# PowerConverter.net
KiCad netlist of a schematic drawn in Altium Designer
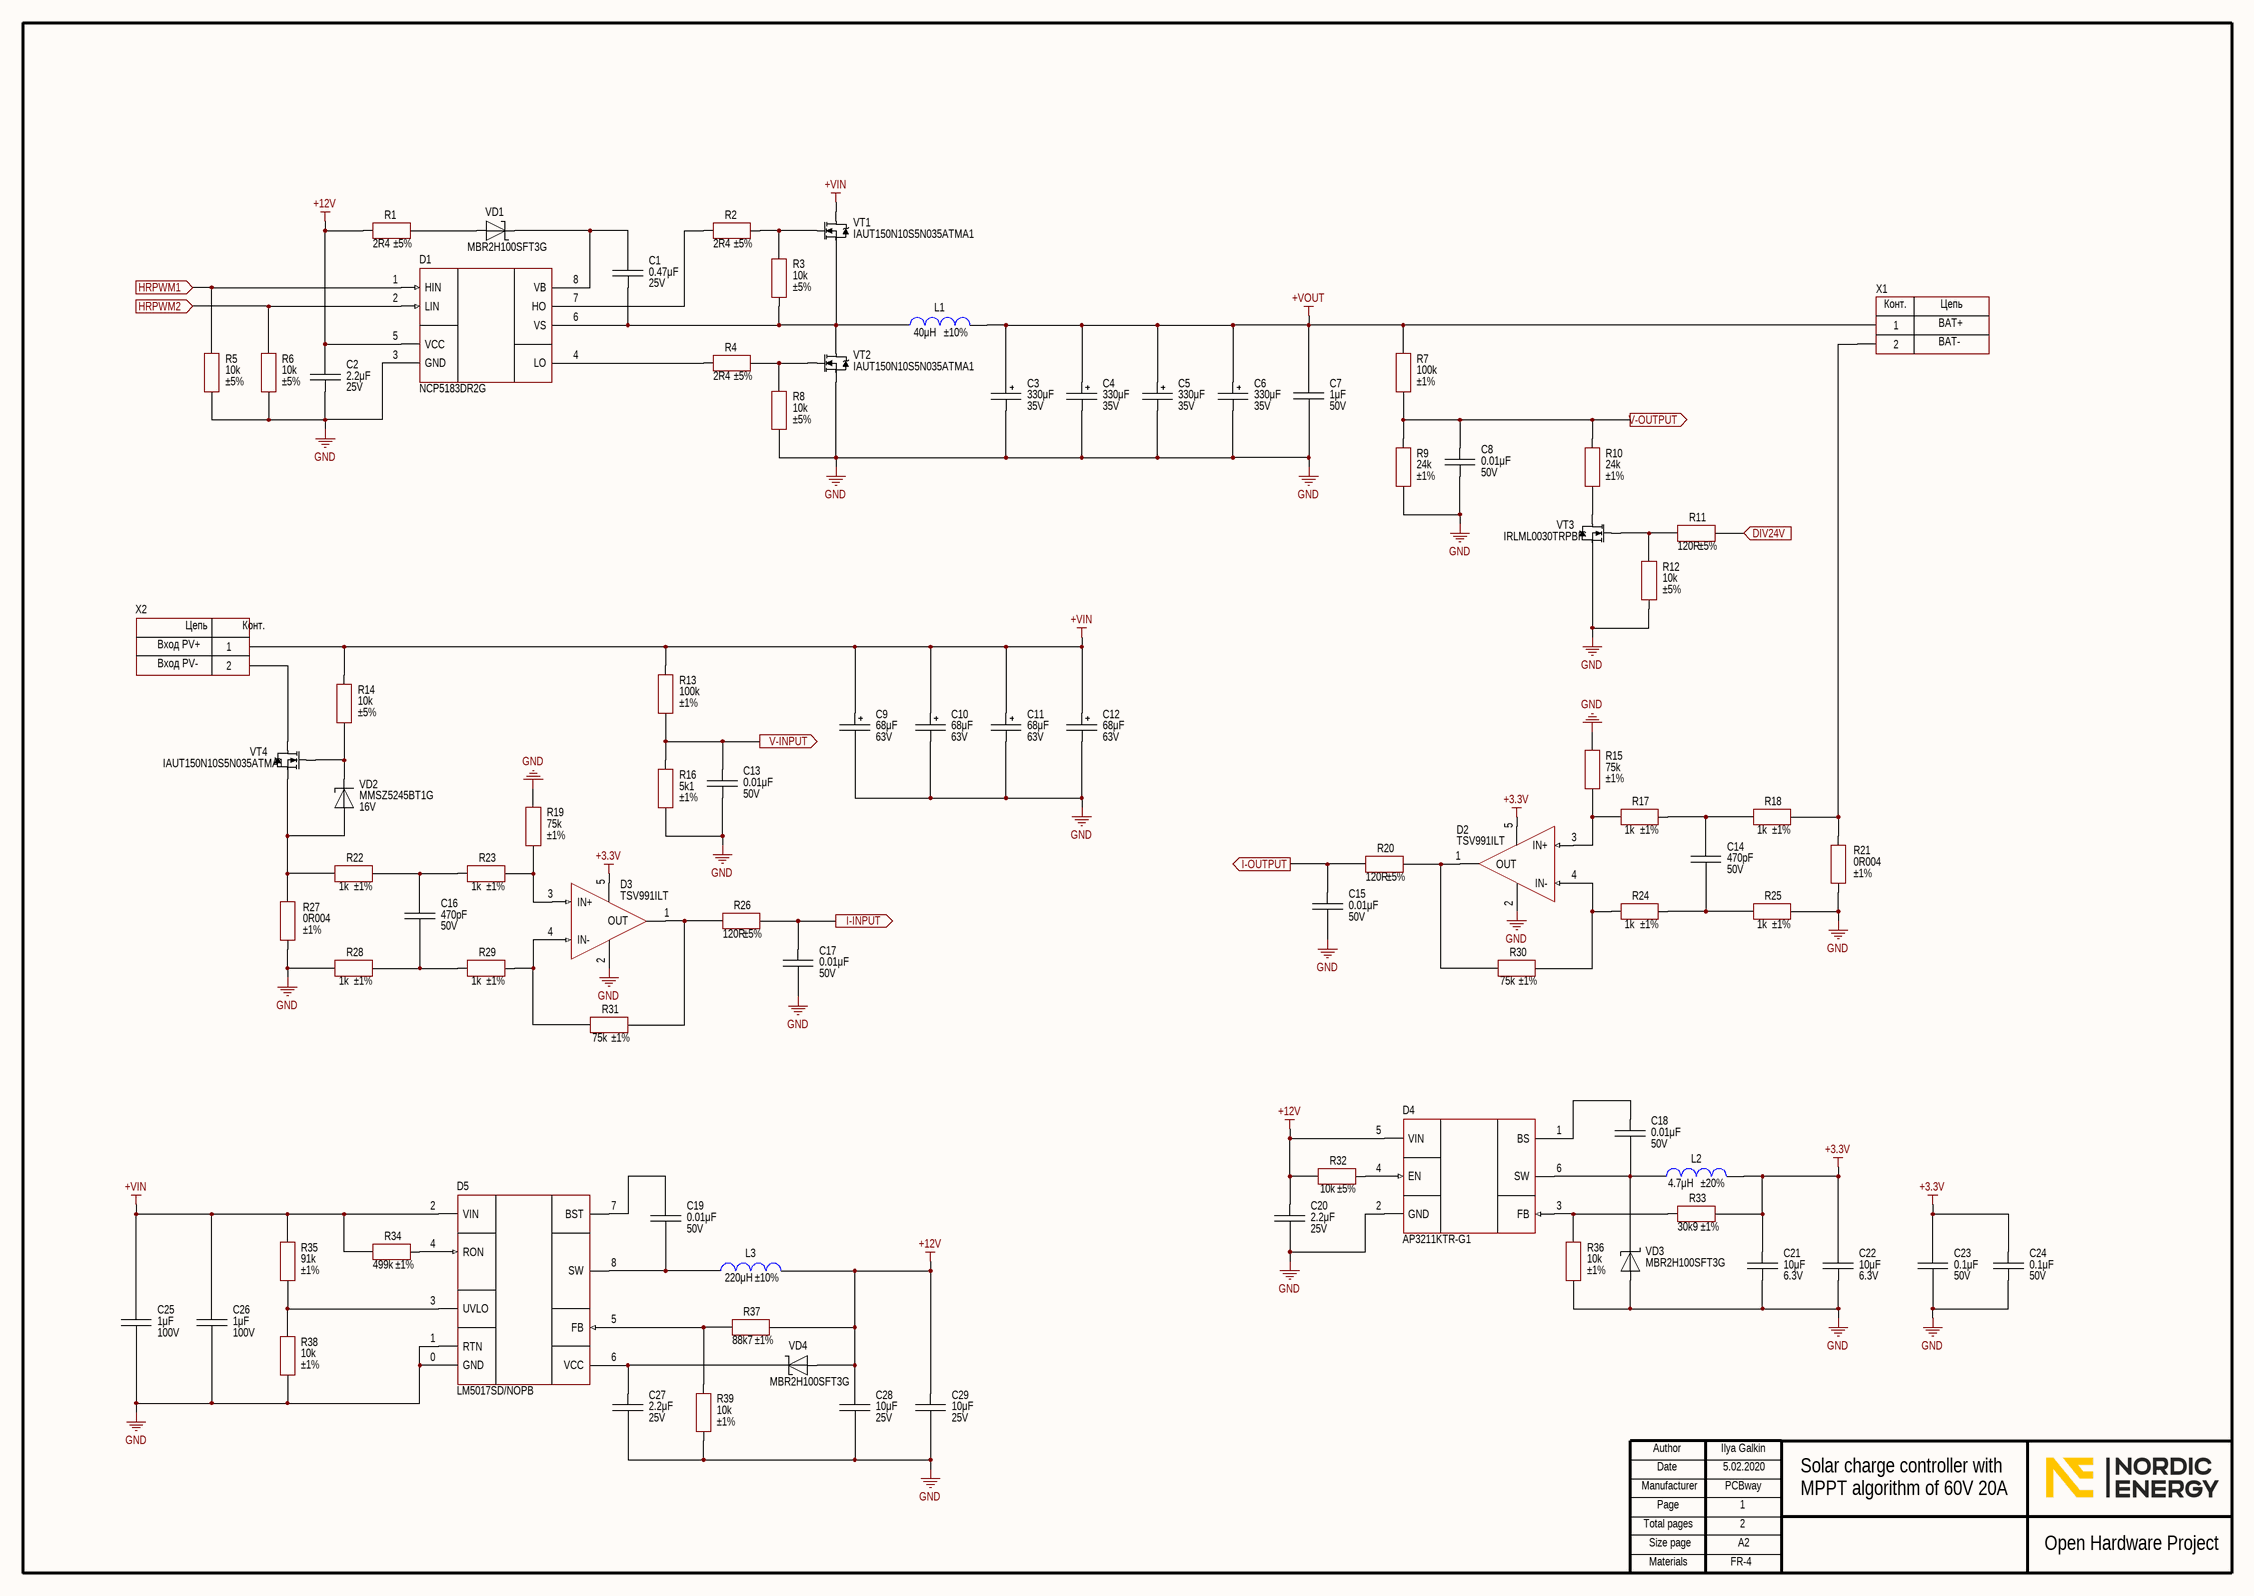
[diagram p0: PowerConverter.SchDoc]

(export (version "E")
  (design (tool "Eeschema 10.0.6"))
  (components
    (comp (ref "C1")
      (value "0.47μF")
      (footprint "CAP: 0805")
      (fields
        (field (name "MANUFACTURER") "Samsung")
        (field (name "PARTNUMBER") "CL21B474KAFNNNG")
        (field (name "VALUEMANUFACTURERPARTNUMBER") "Ceramic capacitor, 0.47μF, X7R, ±10%, 25V, 0805, -55...+125°C")
        (field (name "VOLTAGE") "25V")
      )
      (libsource (lib "Capacitor") (part "Ceramic_0805"))
    )
    (comp (ref "C2")
      (value "2.2μF")
      (footprint "CAP: 0805")
      (fields
        (field (name "MANUFACTURER") "Samsung")
        (field (name "PARTNUMBER") "CL21B225KAFNFNE")
        (field (name "VALUEMANUFACTURERPARTNUMBER") "Ceramic capacitor, 2.2μF, X7R, ±10%, 25V, 0805, -55...+125°C")
        (field (name "VOLTAGE") "25V")
      )
      (libsource (lib "Capacitor") (part "Ceramic_0805"))
    )
    (comp (ref "C3")
      (value "330μF")
      (footprint "CAP: D10C5H12.5")
      (fields
        (field (name "MANUFACTURER") "Panasonic")
        (field (name "PARTNUMBER") "35SEK330M")
        (field (name "VALUEMANUFACTURERPARTNUMBER") "Solid polymer capacitor, 330μF, 35V, ±20%, 18mOhm, 13x10x5 mm, -55...+105°C")
        (field (name "VOLTAGE") "35V")
      )
      (libsource (lib "Capacitor") (part "Aluminium"))
    )
    (comp (ref "C4")
      (value "330μF")
      (footprint "CAP: D10C5H12.5")
      (fields
        (field (name "MANUFACTURER") "Panasonic")
        (field (name "PARTNUMBER") "35SEK330M")
        (field (name "VALUEMANUFACTURERPARTNUMBER") "Solid polymer capacitor, 330μF, 35V, ±20%, 18mOhm, 13x10x5 mm, -55...+105°C")
        (field (name "VOLTAGE") "35V")
      )
      (libsource (lib "Capacitor") (part "Aluminium"))
    )
    (comp (ref "C5")
      (value "330μF")
      (footprint "CAP: D10C5H12.5")
      (fields
        (field (name "MANUFACTURER") "Panasonic")
        (field (name "PARTNUMBER") "35SEK330M")
        (field (name "VALUEMANUFACTURERPARTNUMBER") "Solid polymer capacitor, 330μF, 35V, ±20%, 18mOhm, 13x10x5 mm, -55...+105°C")
        (field (name "VOLTAGE") "35V")
      )
      (libsource (lib "Capacitor") (part "Aluminium"))
    )
    (comp (ref "C6")
      (value "330μF")
      (footprint "CAP: D10C5H12.5")
      (fields
        (field (name "MANUFACTURER") "Panasonic")
        (field (name "PARTNUMBER") "35SEK330M")
        (field (name "VALUEMANUFACTURERPARTNUMBER") "Solid polymer capacitor, 330μF, 35V, ±20%, 18mOhm, 13x10x5 mm, -55...+105°C")
        (field (name "VOLTAGE") "35V")
      )
      (libsource (lib "Capacitor") (part "Aluminium"))
    )
    (comp (ref "C7")
      (value "1μF")
      (footprint "CAP: 0805")
      (fields
        (field (name "MANUFACTURER") "Samsung")
        (field (name "PARTNUMBER") "CL21B105KBFNNNG")
        (field (name "VALUEMANUFACTURERPARTNUMBER") "Ceramic capacitor, 1μF, X7R, ±10%, 50V, 0805, -55...+125°C")
        (field (name "VOLTAGE") "50V")
      )
      (libsource (lib "Capacitor") (part "Ceramic_0805"))
    )
    (comp (ref "C8")
      (value "0.01μF")
      (footprint "CAP: 0805")
      (fields
        (field (name "MANUFACTURER") "Samsung")
        (field (name "PARTNUMBER") "CL21B103KBANNNC")
        (field (name "VALUEMANUFACTURERPARTNUMBER") "Ceramic capacitor, 0.01μF, X7R, ±10%, 50V, 0805, -55...+125°C")
        (field (name "VOLTAGE") "50V")
      )
      (libsource (lib "Capacitor") (part "Ceramic_0805"))
    )
    (comp (ref "C9")
      (value "68μF")
      (footprint "CAP: D10C5H12.5")
      (fields
        (field (name "MANUFACTURER") "Panasonic")
        (field (name "PARTNUMBER") "63SXE68M")
        (field (name "VALUEMANUFACTURERPARTNUMBER") "Solid polymer capacitor, 68μF, 63V, ±20%, 25mOhm, 13x10x5 mm, -55...+105°C")
        (field (name "VOLTAGE") "63V")
      )
      (libsource (lib "Capacitor") (part "Aluminium"))
    )
    (comp (ref "C10")
      (value "68μF")
      (footprint "CAP: D10C5H12.5")
      (fields
        (field (name "MANUFACTURER") "Panasonic")
        (field (name "PARTNUMBER") "63SXE68M")
        (field (name "VALUEMANUFACTURERPARTNUMBER") "Solid polymer capacitor, 68μF, 63V, ±20%, 25mOhm, 13x10x5 mm, -55...+105°C")
        (field (name "VOLTAGE") "63V")
      )
      (libsource (lib "Capacitor") (part "Aluminium"))
    )
    (comp (ref "C11")
      (value "68μF")
      (footprint "CAP: D10C5H12.5")
      (fields
        (field (name "MANUFACTURER") "Panasonic")
        (field (name "PARTNUMBER") "63SXE68M")
        (field (name "VALUEMANUFACTURERPARTNUMBER") "Solid polymer capacitor, 68μF, 63V, ±20%, 25mOhm, 13x10x5 mm, -55...+105°C")
        (field (name "VOLTAGE") "63V")
      )
      (libsource (lib "Capacitor") (part "Aluminium"))
    )
    (comp (ref "C12")
      (value "68μF")
      (footprint "CAP: D10C5H12.5")
      (fields
        (field (name "MANUFACTURER") "Panasonic")
        (field (name "PARTNUMBER") "63SXE68M")
        (field (name "VALUEMANUFACTURERPARTNUMBER") "Solid polymer capacitor, 68μF, 63V, ±20%, 25mOhm, 13x10x5 mm, -55...+105°C")
        (field (name "VOLTAGE") "63V")
      )
      (libsource (lib "Capacitor") (part "Aluminium"))
    )
    (comp (ref "C13")
      (value "0.01μF")
      (footprint "CAP: 0805")
      (fields
        (field (name "MANUFACTURER") "Samsung")
        (field (name "PARTNUMBER") "CL21B103KBANNNC")
        (field (name "VALUEMANUFACTURERPARTNUMBER") "Ceramic capacitor, 0.01μF, X7R, ±10%, 50V, 0805, -55...+125°C")
        (field (name "VOLTAGE") "50V")
      )
      (libsource (lib "Capacitor") (part "Ceramic_0805"))
    )
    (comp (ref "C14")
      (value "470pF")
      (footprint "CAP: 0805")
      (fields
        (field (name "MANUFACTURER") "Samsung")
        (field (name "PARTNUMBER") "CL21B471KBANNNC")
        (field (name "VALUEMANUFACTURERPARTNUMBER") "Ceramic capacitor, 470pF, X7R, ±10%, 50V, 0805, -55...+125°C")
        (field (name "VOLTAGE") "50V")
      )
      (libsource (lib "Capacitor") (part "Ceramic_0805"))
    )
    (comp (ref "C15")
      (value "0.01μF")
      (footprint "CAP: 0805")
      (fields
        (field (name "MANUFACTURER") "Samsung")
        (field (name "PARTNUMBER") "CL21B103KBANNNC")
        (field (name "VALUEMANUFACTURERPARTNUMBER") "Ceramic capacitor, 0.01μF, X7R, ±10%, 50V, 0805, -55...+125°C")
        (field (name "VOLTAGE") "50V")
      )
      (libsource (lib "Capacitor") (part "Ceramic_0805"))
    )
    (comp (ref "C16")
      (value "470pF")
      (footprint "CAP: 0805")
      (fields
        (field (name "MANUFACTURER") "Samsung")
        (field (name "PARTNUMBER") "CL21B471KBANNNC")
        (field (name "VALUEMANUFACTURERPARTNUMBER") "Ceramic capacitor, 470pF, X7R, ±10%, 50V, 0805, -55...+125°C")
        (field (name "VOLTAGE") "50V")
      )
      (libsource (lib "Capacitor") (part "Ceramic_0805"))
    )
    (comp (ref "C17")
      (value "0.01μF")
      (footprint "CAP: 0805")
      (fields
        (field (name "MANUFACTURER") "Samsung")
        (field (name "PARTNUMBER") "CL21B103KBANNNC")
        (field (name "VALUEMANUFACTURERPARTNUMBER") "Ceramic capacitor, 0.01μF, X7R, ±10%, 50V, 0805, -55...+125°C")
        (field (name "VOLTAGE") "50V")
      )
      (libsource (lib "Capacitor") (part "Ceramic_0805"))
    )
    (comp (ref "C18")
      (value "0.01μF")
      (footprint "CAP: 0805")
      (fields
        (field (name "MANUFACTURER") "Samsung")
        (field (name "PARTNUMBER") "CL21B103KBANNNC")
        (field (name "VALUEMANUFACTURERPARTNUMBER") "Ceramic capacitor, 0.01μF, X7R, ±10%, 50V, 0805, -55...+125°C")
        (field (name "VOLTAGE") "50V")
      )
      (libsource (lib "Capacitor") (part "Ceramic_0805"))
    )
    (comp (ref "C19")
      (value "0.01μF")
      (footprint "CAP: 0805")
      (fields
        (field (name "MANUFACTURER") "Samsung")
        (field (name "PARTNUMBER") "CL21B103KBANNNC")
        (field (name "VALUEMANUFACTURERPARTNUMBER") "Ceramic capacitor, 0.01μF, X7R, ±10%, 50V, 0805, -55...+125°C")
        (field (name "VOLTAGE") "50V")
      )
      (libsource (lib "Capacitor") (part "Ceramic_0805"))
    )
    (comp (ref "C20")
      (value "2.2μF")
      (footprint "CAP: 0805")
      (fields
        (field (name "MANUFACTURER") "Samsung")
        (field (name "PARTNUMBER") "CL21B225KAFNFNE")
        (field (name "VALUEMANUFACTURERPARTNUMBER") "Ceramic capacitor, 2.2μF, X7R, ±10%, 25V, 0805, -55...+125°C")
        (field (name "VOLTAGE") "25V")
      )
      (libsource (lib "Capacitor") (part "Ceramic_0805"))
    )
    (comp (ref "C21")
      (value "10μF")
      (footprint "CAP: 0805")
      (fields
        (field (name "MANUFACTURER") "Samsung")
        (field (name "PARTNUMBER") "CL21B106KQQNNNG")
        (field (name "VALUEMANUFACTURERPARTNUMBER") "Ceramic capacitor, 10μF, X7R, ±10%, 6.3V, 0805, -55...+125°C")
        (field (name "VOLTAGE") "6.3V")
      )
      (libsource (lib "Capacitor") (part "Ceramic_0805"))
    )
    (comp (ref "C22")
      (value "10μF")
      (footprint "CAP: 0805")
      (fields
        (field (name "MANUFACTURER") "Samsung")
        (field (name "PARTNUMBER") "CL21B106KQQNNNG")
        (field (name "VALUEMANUFACTURERPARTNUMBER") "Ceramic capacitor, 10μF, X7R, ±10%, 6.3V, 0805, -55...+125°C")
        (field (name "VOLTAGE") "6.3V")
      )
      (libsource (lib "Capacitor") (part "Ceramic_0805"))
    )
    (comp (ref "C23")
      (value "0.1μF")
      (footprint "CAP: 0805")
      (fields
        (field (name "MANUFACTURER") "Samsung")
        (field (name "PARTNUMBER") "CL21B104KBCNFNC")
        (field (name "VALUEMANUFACTURERPARTNUMBER") "Ceramic capacitor, 0.1μF, X7R, ±10%, 50V, 0805, -55...+125°C")
        (field (name "VOLTAGE") "50V")
      )
      (libsource (lib "Capacitor") (part "Ceramic_0805"))
    )
    (comp (ref "C24")
      (value "0.1μF")
      (footprint "CAP: 0805")
      (fields
        (field (name "MANUFACTURER") "Samsung")
        (field (name "PARTNUMBER") "CL21B104KBCNFNC")
        (field (name "VALUEMANUFACTURERPARTNUMBER") "Ceramic capacitor, 0.1μF, X7R, ±10%, 50V, 0805, -55...+125°C")
        (field (name "VOLTAGE") "50V")
      )
      (libsource (lib "Capacitor") (part "Ceramic_0805"))
    )
    (comp (ref "C25")
      (value "1μF")
      (footprint "CAP: 1206")
      (fields
        (field (name "MANUFACTURER") "Samsung")
        (field (name "PARTNUMBER") "CL31B105KCHSNNE")
        (field (name "VALUEMANUFACTURERPARTNUMBER") "Ceramic capacitor, 1μF, X7R, ±10%, 100V, 1206, -55...+125°C")
        (field (name "VOLTAGE") "100V")
      )
      (libsource (lib "Capacitor") (part "Ceramic_1206"))
    )
    (comp (ref "C26")
      (value "1μF")
      (footprint "CAP: 1206")
      (fields
        (field (name "MANUFACTURER") "Samsung")
        (field (name "PARTNUMBER") "CL31B105KCHSNNE")
        (field (name "VALUEMANUFACTURERPARTNUMBER") "Ceramic capacitor, 1μF, X7R, ±10%, 100V, 1206, -55...+125°C")
        (field (name "VOLTAGE") "100V")
      )
      (libsource (lib "Capacitor") (part "Ceramic_1206"))
    )
    (comp (ref "C27")
      (value "2.2μF")
      (footprint "CAP: 0805")
      (fields
        (field (name "MANUFACTURER") "Samsung")
        (field (name "PARTNUMBER") "CL21B225KAFNFNE")
        (field (name "VALUEMANUFACTURERPARTNUMBER") "Ceramic capacitor, 2.2μF, X7R, ±10%, 25V, 0805, -55...+125°C")
        (field (name "VOLTAGE") "25V")
      )
      (libsource (lib "Capacitor") (part "Ceramic_0805"))
    )
    (comp (ref "C28")
      (value "10μF")
      (footprint "CAP: 1206")
      (fields
        (field (name "MANUFACTURER") "Samsung")
        (field (name "PARTNUMBER") "CL31B106KAHNNNE")
        (field (name "VALUEMANUFACTURERPARTNUMBER") "Ceramic capacitor, 10μF, X7R, ±10%, 25V, 1206, -55...+125°C")
        (field (name "VOLTAGE") "25V")
      )
      (libsource (lib "Capacitor") (part "Ceramic_1206"))
    )
    (comp (ref "C29")
      (value "10μF")
      (footprint "CAP: 1206")
      (fields
        (field (name "MANUFACTURER") "Samsung")
        (field (name "PARTNUMBER") "CL31B106KAHNNNE")
        (field (name "VALUEMANUFACTURERPARTNUMBER") "Ceramic capacitor, 10μF, X7R, ±10%, 25V, 1206, -55...+125°C")
        (field (name "VOLTAGE") "25V")
      )
      (libsource (lib "Capacitor") (part "Ceramic_1206"))
    )
    (comp (ref "D1")
      (value "~")
      (footprint "8-SOIC")
      (description "Gate driver")
      (fields
        (field (name "MANUFACTURER") "ON Semiconductor")
        (field (name "VALUEMANUFACTURERPARTNUMBER") "Half-bridge gate driver, 600V, 500kHz, ±4.3A, supply 9...18V, -40...+125°C, 8-SOIC")
        (field (name "PARTNUMBER") "NCP5183DR2G")
      )
      (libsource (lib "IC. Gate driver") (part "NCP5183DR2G"))
    )
    (comp (ref "D2")
      (value "~")
      (footprint "SOT23-5")
      (description "OP amplifier")
      (fields
        (field (name "MANUFACTURER") "STMicroelectronics")
        (field (name "VALUEMANUFACTURERPARTNUMBER") "IC op amplifier, Rail-to-Rail, 20 MHz, 2.7...5.5V, -40...+125°C, SOT23-5")
        (field (name "PARTNUMBER") "TSV991ILT")
      )
      (libsource (lib "IC. Amplifier") (part "TSV991ILT"))
    )
    (comp (ref "D3")
      (value "~")
      (footprint "SOT23-5")
      (description "OP amplifier")
      (fields
        (field (name "MANUFACTURER") "STMicroelectronics")
        (field (name "VALUEMANUFACTURERPARTNUMBER") "IC op amplifier, Rail-to-Rail, 20 MHz, 2.7...5.5V, -40...+125°C, SOT23-5")
        (field (name "PARTNUMBER") "TSV991ILT")
      )
      (libsource (lib "IC. Amplifier") (part "TSV991ILT"))
    )
    (comp (ref "D4")
      (value "~")
      (footprint "SOT23-6")
      (description "Buck converter")
      (fields
        (field (name "MANUFACTURER") "Diodes Incorporated")
        (field (name "VALUEMANUFACTURERPARTNUMBER") "DC/DC buck converter, input 4.5...18V, 1.4MHz, output 0.81...15V, 1.5A, -40...+85°C, SOT23-6")
        (field (name "PARTNUMBER") "AP3211KTR-G1")
      )
      (libsource (lib "IC. Power supply") (part "AP3211KTR-G1"))
    )
    (comp (ref "D5")
      (value "~")
      (footprint "8-WSON (4x4)")
      (description "Buck converter")
      (fields
        (field (name "MANUFACTURER") "Texas Instruments")
        (field (name "VALUEMANUFACTURERPARTNUMBER") "DC/DC buck converter, input 7.5...100V, 1MHz, output 1.225...90V, 0.6A, -40...+125°C, 8-WSON")
        (field (name "PARTNUMBER") "LM5017SD/NOPB")
      )
      (libsource (lib "IC. Power supply") (part "LM5017SD"))
    )
    (comp (ref "L1")
      (value "40μH")
      (footprint "IND: R32.8/20.1/10.7 (L)")
      (fields
        (field (name "MANUFACTURER") "Magnetics")
        (field (name "PARTNUMBER") "0077548A7")
        (field (name "VALUEMANUFACTURERPARTNUMBER") "Fixed inductor, 40μH, ±10%, R32.8/20.1/10.7, Kool Mu, µ=125, 127 нГн/витков2")
        (field (name "TOLERANCE") "±10%")
      )
      (libsource (lib "Inductor") (part "Inductor_R32.8/20.1/10.7"))
    )
    (comp (ref "L2")
      (value "4.7μH")
      (footprint "IND: SDR0403")
      (fields
        (field (name "MANUFACTURER") "Bourns")
        (field (name "PARTNUMBER") "SDR0403-4R7ML")
        (field (name "VALUEMANUFACTURERPARTNUMBER") "Fixed inductor, 4.7μH, ±20%, SDR0403, 1.7A, -40...+125°C")
        (field (name "TOLERANCE") "±20%")
      )
      (libsource (lib "Inductor") (part "Inductor_SDR0403"))
    )
    (comp (ref "L3")
      (value "220μH")
      (footprint "IND: SDR0805")
      (fields
        (field (name "MANUFACTURER") "Bourns")
        (field (name "PARTNUMBER") "SDR0805-221KL")
        (field (name "VALUEMANUFACTURERPARTNUMBER") "Fixed inductor, 220μH, ±10%, SDR0805, 490mA, -40...+125°C")
        (field (name "TOLERANCE") "±10%")
      )
      (libsource (lib "Inductor") (part "Inductor_SDR0805"))
    )
    (comp (ref "R1")
      (value "2R4")
      (footprint "RES: 0805")
      (fields
        (field (name "MANUFACTURER") "Yageo")
        (field (name "PARTNUMBER") "RC0805JR-072R4L")
        (field (name "VALUEMANUFACTURERPARTNUMBER") "Resistor film, 2R4, ±5%, 0805, 0.125W, -55...+125°C")
        (field (name "TOLERANCE") "±5%")
      )
      (libsource (lib "Resistor") (part "Resistor_0805"))
    )
    (comp (ref "R2")
      (value "2R4")
      (footprint "RES: 0805")
      (fields
        (field (name "MANUFACTURER") "Yageo")
        (field (name "PARTNUMBER") "RC0805JR-072R4L")
        (field (name "VALUEMANUFACTURERPARTNUMBER") "Resistor film, 2R4, ±5%, 0805, 0.125W, -55...+125°C")
        (field (name "TOLERANCE") "±5%")
      )
      (libsource (lib "Resistor") (part "Resistor_0805"))
    )
    (comp (ref "R3")
      (value "10k")
      (footprint "RES: 0805")
      (fields
        (field (name "MANUFACTURER") "Yageo")
        (field (name "PARTNUMBER") "RC0805JR-0710KL")
        (field (name "VALUEMANUFACTURERPARTNUMBER") "Resistor film, 10k, ±5%, 0805, 0.125W, -55...+125°C")
        (field (name "TOLERANCE") "±5%")
      )
      (libsource (lib "") (part "Resistor_0805_1"))
    )
    (comp (ref "R4")
      (value "2R4")
      (footprint "RES: 0805")
      (fields
        (field (name "MANUFACTURER") "Yageo")
        (field (name "PARTNUMBER") "RC0805JR-072R4L")
        (field (name "VALUEMANUFACTURERPARTNUMBER") "Resistor film, 2R4, ±5%, 0805, 0.125W, -55...+125°C")
        (field (name "TOLERANCE") "±5%")
      )
      (libsource (lib "Resistor") (part "Resistor_0805"))
    )
    (comp (ref "R5")
      (value "10k")
      (footprint "RES: 0805")
      (fields
        (field (name "MANUFACTURER") "Yageo")
        (field (name "PARTNUMBER") "RC0805JR-0710KL")
        (field (name "VALUEMANUFACTURERPARTNUMBER") "Resistor film, 10k, ±5%, 0805, 0.125W, -55...+125°C")
        (field (name "TOLERANCE") "±5%")
      )
      (libsource (lib "") (part "Resistor_0805_1"))
    )
    (comp (ref "R6")
      (value "10k")
      (footprint "RES: 0805")
      (fields
        (field (name "MANUFACTURER") "Yageo")
        (field (name "PARTNUMBER") "RC0805JR-0710KL")
        (field (name "VALUEMANUFACTURERPARTNUMBER") "Resistor film, 10k, ±5%, 0805, 0.125W, -55...+125°C")
        (field (name "TOLERANCE") "±5%")
      )
      (libsource (lib "") (part "Resistor_0805_1"))
    )
    (comp (ref "R7")
      (value "100k")
      (footprint "RES: 0805")
      (fields
        (field (name "MANUFACTURER") "Yageo")
        (field (name "PARTNUMBER") "RC0805FR-07100KL")
        (field (name "VALUEMANUFACTURERPARTNUMBER") "Resistor film, 100k, ±1%, 0805, 0.125W, -55...+125°C")
        (field (name "TOLERANCE") "±1%")
      )
      (libsource (lib "") (part "Resistor_0805_1"))
    )
    (comp (ref "R8")
      (value "10k")
      (footprint "RES: 0805")
      (fields
        (field (name "MANUFACTURER") "Yageo")
        (field (name "PARTNUMBER") "RC0805JR-0710KL")
        (field (name "VALUEMANUFACTURERPARTNUMBER") "Resistor film, 10k, ±5%, 0805, 0.125W, -55...+125°C")
        (field (name "TOLERANCE") "±5%")
      )
      (libsource (lib "") (part "Resistor_0805_1"))
    )
    (comp (ref "R9")
      (value "24k")
      (footprint "RES: 0805")
      (fields
        (field (name "MANUFACTURER") "Yageo")
        (field (name "PARTNUMBER") "RC0805FR-0724KL")
        (field (name "VALUEMANUFACTURERPARTNUMBER") "Resistor film, 24k, ±1%, 0805, 0.125W, -55...+125°C")
        (field (name "TOLERANCE") "±1%")
      )
      (libsource (lib "") (part "Resistor_0805_1"))
    )
    (comp (ref "R10")
      (value "24k")
      (footprint "RES: 0805")
      (fields
        (field (name "MANUFACTURER") "Yageo")
        (field (name "PARTNUMBER") "RC0805FR-0724KL")
        (field (name "VALUEMANUFACTURERPARTNUMBER") "Resistor film, 24k, ±1%, 0805, 0.125W, -55...+125°C")
        (field (name "TOLERANCE") "±1%")
      )
      (libsource (lib "") (part "Resistor_0805_1"))
    )
    (comp (ref "R11")
      (value "120R")
      (footprint "RES: 0805")
      (fields
        (field (name "MANUFACTURER") "Yageo")
        (field (name "PARTNUMBER") "RC0805JR-07120RL")
        (field (name "VALUEMANUFACTURERPARTNUMBER") "Resistor film, 120R, ±5%, 0805, 0.125W, -55...+125°C")
        (field (name "TOLERANCE") "±5%")
      )
      (libsource (lib "Resistor") (part "Resistor_0805"))
    )
    (comp (ref "R12")
      (value "10k")
      (footprint "RES: 0805")
      (fields
        (field (name "MANUFACTURER") "Yageo")
        (field (name "PARTNUMBER") "RC0805JR-0710KL")
        (field (name "VALUEMANUFACTURERPARTNUMBER") "Resistor film, 10k, ±5%, 0805, 0.125W, -55...+125°C")
        (field (name "TOLERANCE") "±5%")
      )
      (libsource (lib "") (part "Resistor_0805_1"))
    )
    (comp (ref "R13")
      (value "100k")
      (footprint "RES: 0805")
      (fields
        (field (name "MANUFACTURER") "Yageo")
        (field (name "PARTNUMBER") "RC0805FR-07100KL")
        (field (name "VALUEMANUFACTURERPARTNUMBER") "Resistor film, 100k, ±1%, 0805, 0.125W, -55...+125°C")
        (field (name "TOLERANCE") "±1%")
      )
      (libsource (lib "") (part "Resistor_0805_1"))
    )
    (comp (ref "R14")
      (value "10k")
      (footprint "RES: 0805")
      (fields
        (field (name "MANUFACTURER") "Yageo")
        (field (name "PARTNUMBER") "RC0805JR-0710KL")
        (field (name "VALUEMANUFACTURERPARTNUMBER") "Resistor film, 10k, ±5%, 0805, 0.125W, -55...+125°C")
        (field (name "TOLERANCE") "±5%")
      )
      (libsource (lib "") (part "Resistor_0805_1"))
    )
    (comp (ref "R15")
      (value "75k")
      (footprint "RES: 0805")
      (fields
        (field (name "MANUFACTURER") "Yageo")
        (field (name "PARTNUMBER") "RC0805FR-0775KL")
        (field (name "VALUEMANUFACTURERPARTNUMBER") "Resistor film, 75k, ±1%, 0805, 0.125W, -55...+125°C")
        (field (name "TOLERANCE") "±1%")
      )
      (libsource (lib "") (part "Resistor_0805_1"))
    )
    (comp (ref "R16")
      (value "5k1")
      (footprint "RES: 0805")
      (fields
        (field (name "MANUFACTURER") "Yageo")
        (field (name "PARTNUMBER") "RC0805FR-075K1L")
        (field (name "VALUEMANUFACTURERPARTNUMBER") "Resistor film, 5k1, ±1%, 0805, 0.125W, -55...+125°C")
        (field (name "TOLERANCE") "±1%")
      )
      (libsource (lib "") (part "Resistor_0805_1"))
    )
    (comp (ref "R17")
      (value "1k")
      (footprint "RES: 0805")
      (fields
        (field (name "MANUFACTURER") "Yageo")
        (field (name "PARTNUMBER") "RC0805FR-071KL")
        (field (name "VALUEMANUFACTURERPARTNUMBER") "Resistor film, 1k, ±1%, 0805, 0.125W, -55...+125°C")
        (field (name "TOLERANCE") "±1%")
      )
      (libsource (lib "Resistor") (part "Resistor_0805"))
    )
    (comp (ref "R18")
      (value "1k")
      (footprint "RES: 0805")
      (fields
        (field (name "MANUFACTURER") "Yageo")
        (field (name "PARTNUMBER") "RC0805FR-071KL")
        (field (name "VALUEMANUFACTURERPARTNUMBER") "Resistor film, 1k, ±1%, 0805, 0.125W, -55...+125°C")
        (field (name "TOLERANCE") "±1%")
      )
      (libsource (lib "Resistor") (part "Resistor_0805"))
    )
    (comp (ref "R19")
      (value "75k")
      (footprint "RES: 0805")
      (fields
        (field (name "MANUFACTURER") "Yageo")
        (field (name "PARTNUMBER") "RC0805FR-0775KL")
        (field (name "VALUEMANUFACTURERPARTNUMBER") "Resistor film, 75k, ±1%, 0805, 0.125W, -55...+125°C")
        (field (name "TOLERANCE") "±1%")
      )
      (libsource (lib "") (part "Resistor_0805_1"))
    )
    (comp (ref "R20")
      (value "120R")
      (footprint "RES: 0805")
      (fields
        (field (name "MANUFACTURER") "Yageo")
        (field (name "PARTNUMBER") "RC0805JR-07120RL")
        (field (name "VALUEMANUFACTURERPARTNUMBER") "Resistor film, 120R, ±5%, 0805, 0.125W, -55...+125°C")
        (field (name "TOLERANCE") "±5%")
      )
      (libsource (lib "Resistor") (part "Resistor_0805"))
    )
    (comp (ref "R21")
      (value "0R004")
      (footprint "RES: CSS2H (2512)")
      (fields
        (field (name "MANUFACTURER") "Bourns")
        (field (name "PARTNUMBER") "CRE2512-FZ-R004E-3")
        (field (name "VALUEMANUFACTURERPARTNUMBER") "Resistor film, 0R004, ±1%, 2512, 5W, -55...+170°C")
        (field (name "TOLERANCE") "±1%")
      )
      (libsource (lib "Resistor") (part "Shunt"))
    )
    (comp (ref "R22")
      (value "1k")
      (footprint "RES: 0805")
      (fields
        (field (name "MANUFACTURER") "Yageo")
        (field (name "PARTNUMBER") "RC0805FR-071KL")
        (field (name "VALUEMANUFACTURERPARTNUMBER") "Resistor film, 1k, ±1%, 0805, 0.125W, -55...+125°C")
        (field (name "TOLERANCE") "±1%")
      )
      (libsource (lib "Resistor") (part "Resistor_0805"))
    )
    (comp (ref "R23")
      (value "1k")
      (footprint "RES: 0805")
      (fields
        (field (name "MANUFACTURER") "Yageo")
        (field (name "PARTNUMBER") "RC0805FR-071KL")
        (field (name "VALUEMANUFACTURERPARTNUMBER") "Resistor film, 1k, ±1%, 0805, 0.125W, -55...+125°C")
        (field (name "TOLERANCE") "±1%")
      )
      (libsource (lib "Resistor") (part "Resistor_0805"))
    )
    (comp (ref "R24")
      (value "1k")
      (footprint "RES: 0805")
      (fields
        (field (name "MANUFACTURER") "Yageo")
        (field (name "PARTNUMBER") "RC0805FR-071KL")
        (field (name "VALUEMANUFACTURERPARTNUMBER") "Resistor film, 1k, ±1%, 0805, 0.125W, -55...+125°C")
        (field (name "TOLERANCE") "±1%")
      )
      (libsource (lib "Resistor") (part "Resistor_0805"))
    )
    (comp (ref "R25")
      (value "1k")
      (footprint "RES: 0805")
      (fields
        (field (name "MANUFACTURER") "Yageo")
        (field (name "PARTNUMBER") "RC0805FR-071KL")
        (field (name "VALUEMANUFACTURERPARTNUMBER") "Resistor film, 1k, ±1%, 0805, 0.125W, -55...+125°C")
        (field (name "TOLERANCE") "±1%")
      )
      (libsource (lib "Resistor") (part "Resistor_0805"))
    )
    (comp (ref "R26")
      (value "120R")
      (footprint "RES: 0805")
      (fields
        (field (name "MANUFACTURER") "Yageo")
        (field (name "PARTNUMBER") "RC0805JR-07120RL")
        (field (name "VALUEMANUFACTURERPARTNUMBER") "Resistor film, 120R, ±5%, 0805, 0.125W, -55...+125°C")
        (field (name "TOLERANCE") "±5%")
      )
      (libsource (lib "Resistor") (part "Resistor_0805"))
    )
    (comp (ref "R27")
      (value "0R004")
      (footprint "RES: CSS2H (2512)")
      (fields
        (field (name "MANUFACTURER") "Bourns")
        (field (name "PARTNUMBER") "CRE2512-FZ-R004E-3")
        (field (name "VALUEMANUFACTURERPARTNUMBER") "Resistor film, 0R004, ±1%, 2512, 5W, -55...+170°C")
        (field (name "TOLERANCE") "±1%")
      )
      (libsource (lib "Resistor") (part "Shunt"))
    )
    (comp (ref "R28")
      (value "1k")
      (footprint "RES: 0805")
      (fields
        (field (name "MANUFACTURER") "Yageo")
        (field (name "PARTNUMBER") "RC0805FR-071KL")
        (field (name "VALUEMANUFACTURERPARTNUMBER") "Resistor film, 1k, ±1%, 0805, 0.125W, -55...+125°C")
        (field (name "TOLERANCE") "±1%")
      )
      (libsource (lib "Resistor") (part "Resistor_0805"))
    )
    (comp (ref "R29")
      (value "1k")
      (footprint "RES: 0805")
      (fields
        (field (name "MANUFACTURER") "Yageo")
        (field (name "PARTNUMBER") "RC0805FR-071KL")
        (field (name "VALUEMANUFACTURERPARTNUMBER") "Resistor film, 1k, ±1%, 0805, 0.125W, -55...+125°C")
        (field (name "TOLERANCE") "±1%")
      )
      (libsource (lib "Resistor") (part "Resistor_0805"))
    )
    (comp (ref "R30")
      (value "75k")
      (footprint "RES: 0805")
      (fields
        (field (name "MANUFACTURER") "Yageo")
        (field (name "PARTNUMBER") "RC0805FR-0775KL")
        (field (name "VALUEMANUFACTURERPARTNUMBER") "Resistor film, 75k, ±1%, 0805, 0.125W, -55...+125°C")
        (field (name "TOLERANCE") "±1%")
      )
      (libsource (lib "Resistor") (part "Resistor_0805"))
    )
    (comp (ref "R31")
      (value "75k")
      (footprint "RES: 0805")
      (fields
        (field (name "MANUFACTURER") "Yageo")
        (field (name "PARTNUMBER") "RC0805FR-0775KL")
        (field (name "VALUEMANUFACTURERPARTNUMBER") "Resistor film, 75k, ±1%, 0805, 0.125W, -55...+125°C")
        (field (name "TOLERANCE") "±1%")
      )
      (libsource (lib "Resistor") (part "Resistor_0805"))
    )
    (comp (ref "R32")
      (value "10k")
      (footprint "RES: 0805")
      (fields
        (field (name "MANUFACTURER") "Yageo")
        (field (name "PARTNUMBER") "RC0805JR-0710KL")
        (field (name "VALUEMANUFACTURERPARTNUMBER") "Resistor film, 10k, ±5%, 0805, 0.125W, -55...+125°C")
        (field (name "TOLERANCE") "±5%")
      )
      (libsource (lib "Resistor") (part "Resistor_0805"))
    )
    (comp (ref "R33")
      (value "30k9")
      (footprint "RES: 0805")
      (fields
        (field (name "MANUFACTURER") "Yageo")
        (field (name "PARTNUMBER") "RC0805FR-0730K9L")
        (field (name "VALUEMANUFACTURERPARTNUMBER") "Resistor film, 30k9, ±1%, 0805, 0.125W, -55...+125°C")
        (field (name "TOLERANCE") "±1%")
      )
      (libsource (lib "Resistor") (part "Resistor_0805"))
    )
    (comp (ref "R34")
      (value "499k")
      (footprint "RES: 0805")
      (fields
        (field (name "MANUFACTURER") "Yageo")
        (field (name "PARTNUMBER") "RC0805FR-07499KL")
        (field (name "VALUEMANUFACTURERPARTNUMBER") "Resistor film, 499k, ±1%, 0805, 0.125W, -55...+125°C")
        (field (name "TOLERANCE") "±1%")
      )
      (libsource (lib "Resistor") (part "Resistor_0805"))
    )
    (comp (ref "R35")
      (value "91k")
      (footprint "RES: 0805")
      (fields
        (field (name "MANUFACTURER") "Yageo")
        (field (name "PARTNUMBER") "RC0805FR-0791KL")
        (field (name "VALUEMANUFACTURERPARTNUMBER") "Resistor film, 91k, ±1%, 0805, 0.125W, -55...+125°C")
        (field (name "TOLERANCE") "±1%")
      )
      (libsource (lib "") (part "Resistor_0805_1"))
    )
    (comp (ref "R36")
      (value "10k")
      (footprint "RES: 0805")
      (fields
        (field (name "MANUFACTURER") "Yageo")
        (field (name "PARTNUMBER") "RC0805FR-0710KL")
        (field (name "VALUEMANUFACTURERPARTNUMBER") "Resistor film, 10k, ±1%, 0805, 0.125W, -55...+125°C")
        (field (name "TOLERANCE") "±1%")
      )
      (libsource (lib "") (part "Resistor_0805_1"))
    )
    (comp (ref "R37")
      (value "88k7")
      (footprint "RES: 0805")
      (fields
        (field (name "MANUFACTURER") "Yageo")
        (field (name "PARTNUMBER") "RC0805FR-0788K7L")
        (field (name "VALUEMANUFACTURERPARTNUMBER") "Resistor film, 88k7, ±1%, 0805, 0.125W, -55...+125°C")
        (field (name "TOLERANCE") "±1%")
      )
      (libsource (lib "Resistor") (part "Resistor_0805"))
    )
    (comp (ref "R38")
      (value "10k")
      (footprint "RES: 0805")
      (fields
        (field (name "MANUFACTURER") "Yageo")
        (field (name "PARTNUMBER") "RC0805FR-0710KL")
        (field (name "VALUEMANUFACTURERPARTNUMBER") "Resistor film, 10k, ±1%, 0805, 0.125W, -55...+125°C")
        (field (name "TOLERANCE") "±1%")
      )
      (libsource (lib "") (part "Resistor_0805_1"))
    )
    (comp (ref "R39")
      (value "10k")
      (footprint "RES: 0805")
      (fields
        (field (name "MANUFACTURER") "Yageo")
        (field (name "PARTNUMBER") "RC0805FR-0710KL")
        (field (name "VALUEMANUFACTURERPARTNUMBER") "Resistor film, 10k, ±1%, 0805, 0.125W, -55...+125°C")
        (field (name "TOLERANCE") "±1%")
      )
      (libsource (lib "") (part "Resistor_0805_1"))
    )
    (comp (ref "VD1")
      (value "~")
      (footprint "DIODE: SOD123F")
      (fields
        (field (name "MANUFACTURER") "ON Semiconductor")
        (field (name "VALUEMANUFACTURERPARTNUMBER") "Schottky diode, 100V, 2A, 840mV, 15pF, SOD-123F, -55...+150°C")
        (field (name "VOLTAGE") "100V")
        (field (name "PARTNUMBER") "MBR2H100SFT3G")
      )
      (libsource (lib "Diode") (part "Schottky_single"))
    )
    (comp (ref "VD2")
      (value "~")
      (footprint "DIODE: SOD123")
      (fields
        (field (name "MANUFACTURER") "ON Semiconductor")
        (field (name "VALUEMANUFACTURERPARTNUMBER") "Zener diode, 16V, 500mW, 0.9V, 16Ohm, SOD-123, -55...+150°C")
        (field (name "VOLTAGE") "16V")
        (field (name "PARTNUMBER") "MMSZ5245BT1G")
      )
      (libsource (lib "Diode") (part "Zener_single"))
    )
    (comp (ref "VD3")
      (value "~")
      (footprint "DIODE: SOD123F")
      (fields
        (field (name "MANUFACTURER") "ON Semiconductor")
        (field (name "VALUEMANUFACTURERPARTNUMBER") "Schottky diode, 100V, 2A, 840mV, 15pF, SOD-123F, -55...+150°C")
        (field (name "VOLTAGE") "100V")
        (field (name "PARTNUMBER") "MBR2H100SFT3G")
      )
      (libsource (lib "Diode") (part "Schottky_single"))
    )
    (comp (ref "VD4")
      (value "~")
      (footprint "DIODE: SOD123F")
      (fields
        (field (name "MANUFACTURER") "ON Semiconductor")
        (field (name "VALUEMANUFACTURERPARTNUMBER") "Schottky diode, 100V, 2A, 840mV, 15pF, SOD-123F, -55...+150°C")
        (field (name "VOLTAGE") "100V")
        (field (name "PARTNUMBER") "MBR2H100SFT3G")
      )
      (libsource (lib "Diode") (part "Schottky_single"))
    )
    (comp (ref "VT1")
      (value "~")
      (footprint "HSOF-8-1")
      (fields
        (field (name "MANUFACTURER") "Infineon Technologies")
        (field (name "VALUEMANUFACTURERPARTNUMBER") "MOSFET N-channel transistor, 100V, 150A, 87nC, 166W, 3.5mOhm, 6110pF, 8-HSOF, -55...+175°C")
        (field (name "PARTNUMBER") "IAUT150N10S5N035ATMA1")
      )
      (libsource (lib "Transistor") (part "MOSFET_N_123"))
    )
    (comp (ref "VT2")
      (value "~")
      (footprint "HSOF-8-1")
      (fields
        (field (name "MANUFACTURER") "Infineon Technologies")
        (field (name "VALUEMANUFACTURERPARTNUMBER") "MOSFET N-channel transistor, 100V, 150A, 87nC, 166W, 3.5mOhm, 6110pF, 8-HSOF, -55...+175°C")
        (field (name "PARTNUMBER") "IAUT150N10S5N035ATMA1")
      )
      (libsource (lib "Transistor") (part "MOSFET_N_123"))
    )
    (comp (ref "VT3")
      (value "~")
      (footprint "SOT23")
      (fields
        (field (name "MANUFACTURER") "Infineon Technologies")
        (field (name "VALUEMANUFACTURERPARTNUMBER") "MOSFET N-channel transistor, 30V, 5.3A, 2.6nC, 1.3W, 27mOhm, 382pF, SOT-23, -55...+150°C")
        (field (name "PARTNUMBER") "IRLML0030TRPBF")
      )
      (libsource (lib "Transistor") (part "MOSFET_N_132"))
    )
    (comp (ref "VT4")
      (value "~")
      (footprint "HSOF-8-1")
      (fields
        (field (name "MANUFACTURER") "Infineon Technologies")
        (field (name "VALUEMANUFACTURERPARTNUMBER") "MOSFET N-channel transistor, 100V, 150A, 87nC, 166W, 3.5mOhm, 6110pF, 8-HSOF, -55...+175°C")
        (field (name "PARTNUMBER") "IAUT150N10S5N035ATMA1")
      )
      (libsource (lib "Transistor") (part "MOSFET_N_123"))
    )
    (comp (ref "X1")
      (value "~")
      (footprint "CON: XT60PW-M")
      (fields
        (field (name "MANUFACTURER") "AMASS")
        (field (name "VALUEMANUFACTURERPARTNUMBER") "Power connector, 2pin, 7.2mm, 500V, 60A")
        (field (name "PARTNUMBER") "XT60PW-M")
      )
      (libsource (lib "") (part "Connector_XT_2pin_1"))
    )
    (comp (ref "X2")
      (value "~")
      (footprint "CON: XT60PW-M")
      (fields
        (field (name "MANUFACTURER") "AMASS")
        (field (name "VALUEMANUFACTURERPARTNUMBER") "Power connector, 2pin, 7.2mm, 500V, 60A")
        (field (name "PARTNUMBER") "XT60PW-M")
      )
      (libsource (lib "Connector") (part "Connector_XT_2pin"))
    )
  )
  (nets
    (net (code "1") (name "+3.3V") (class "Default")
      (node (ref "C21") (pin "2") (pinfunction "2_2") (pintype "power_in"))
      (node (ref "C22") (pin "2") (pinfunction "2_2") (pintype "power_in"))
      (node (ref "C23") (pin "2") (pinfunction "2_2") (pintype "power_in"))
      (node (ref "C24") (pin "2") (pinfunction "2_2") (pintype "power_in"))
      (node (ref "D2") (pin "5") (pinfunction "V+_5") (pintype "power_in"))
      (node (ref "D3") (pin "5") (pinfunction "V+_5") (pintype "power_in"))
      (node (ref "L2") (pin "1") (pinfunction "1_1") (pintype "passive"))
      (node (ref "R33") (pin "1") (pinfunction "1_1") (pintype "passive"))
    )
    (net (code "2") (name "+12V") (class "Default")
      (node (ref "C2") (pin "2") (pinfunction "2_2") (pintype "power_in"))
      (node (ref "C20") (pin "2") (pinfunction "2_2") (pintype "power_in"))
      (node (ref "C28") (pin "2") (pinfunction "2_2") (pintype "power_in"))
      (node (ref "C29") (pin "2") (pinfunction "2_2") (pintype "power_in"))
      (node (ref "D1") (pin "5") (pinfunction "VCC_5") (pintype "passive"))
      (node (ref "D4") (pin "5") (pinfunction "VIN_5") (pintype "passive"))
      (node (ref "L3") (pin "1") (pinfunction "1_1") (pintype "passive"))
      (node (ref "R1") (pin "2") (pinfunction "2_2") (pintype "passive"))
      (node (ref "R32") (pin "2") (pinfunction "2_2") (pintype "passive"))
      (node (ref "R37") (pin "1") (pinfunction "1_1") (pintype "passive"))
      (node (ref "VD4") (pin "1") (pinfunction "1_1") (pintype "passive"))
    )
    (net (code "3") (name "+VIN") (class "Default")
      (node (ref "C10") (pin "1") (pinfunction "1_1") (pintype "power_in"))
      (node (ref "C11") (pin "1") (pinfunction "1_1") (pintype "power_in"))
      (node (ref "C12") (pin "1") (pinfunction "1_1") (pintype "power_in"))
      (node (ref "C25") (pin "2") (pinfunction "2_2") (pintype "power_in"))
      (node (ref "C26") (pin "2") (pinfunction "2_2") (pintype "power_in"))
      (node (ref "C9") (pin "1") (pinfunction "1_1") (pintype "power_in"))
      (node (ref "D5") (pin "2") (pinfunction "VIN_2") (pintype "passive"))
      (node (ref "R13") (pin "2") (pinfunction "2_2") (pintype "passive"))
      (node (ref "R14") (pin "2") (pinfunction "2_2") (pintype "passive"))
      (node (ref "R34") (pin "2") (pinfunction "2_2") (pintype "passive"))
      (node (ref "R35") (pin "2") (pinfunction "2_2") (pintype "passive"))
      (node (ref "VT1") (pin "2") (pinfunction "D_2") (pintype "passive"))
      (node (ref "X2") (pin "1") (pinfunction "1_1") (pintype "passive"))
    )
    (net (code "4") (name "+VOUT") (class "Default")
      (node (ref "C3") (pin "1") (pinfunction "1_1") (pintype "power_in"))
      (node (ref "C4") (pin "1") (pinfunction "1_1") (pintype "power_in"))
      (node (ref "C5") (pin "1") (pinfunction "1_1") (pintype "power_in"))
      (node (ref "C6") (pin "1") (pinfunction "1_1") (pintype "power_in"))
      (node (ref "C7") (pin "2") (pinfunction "2_2") (pintype "power_in"))
      (node (ref "L1") (pin "1") (pinfunction "1_1") (pintype "passive"))
      (node (ref "R7") (pin "2") (pinfunction "2_2") (pintype "passive"))
      (node (ref "X1") (pin "1") (pinfunction "1_1") (pintype "passive"))
    )
    (net (code "5") (name "/DIV24V") (class "Default")
      (node (ref "R11") (pin "1") (pinfunction "1_1") (pintype "passive"))
    )
    (net (code "6") (name "/HRPWM1") (class "Default")
      (node (ref "D1") (pin "1") (pinfunction "HIN_1") (pintype "input"))
      (node (ref "R5") (pin "2") (pinfunction "2_2") (pintype "passive"))
    )
    (net (code "7") (name "/HRPWM2") (class "Default")
      (node (ref "D1") (pin "2") (pinfunction "LIN_2") (pintype "input"))
      (node (ref "R6") (pin "2") (pinfunction "2_2") (pintype "passive"))
    )
    (net (code "8") (name "/I-INPUT") (class "Default")
      (node (ref "C17") (pin "2") (pinfunction "2_2") (pintype "power_in"))
      (node (ref "R26") (pin "1") (pinfunction "1_1") (pintype "passive"))
    )
    (net (code "9") (name "/I-OUTPUT") (class "Default")
      (node (ref "C15") (pin "2") (pinfunction "2_2") (pintype "power_in"))
      (node (ref "R20") (pin "2") (pinfunction "2_2") (pintype "passive"))
    )
    (net (code "10") (name "/V-INPUT") (class "Default")
      (node (ref "C13") (pin "2") (pinfunction "2_2") (pintype "power_in"))
      (node (ref "R13") (pin "1") (pinfunction "1_1") (pintype "passive"))
      (node (ref "R16") (pin "2") (pinfunction "2_2") (pintype "passive"))
    )
    (net (code "11") (name "/V-OUTPUT") (class "Default")
      (node (ref "C8") (pin "2") (pinfunction "2_2") (pintype "power_in"))
      (node (ref "R10") (pin "2") (pinfunction "2_2") (pintype "passive"))
      (node (ref "R7") (pin "1") (pinfunction "1_1") (pintype "passive"))
      (node (ref "R9") (pin "2") (pinfunction "2_2") (pintype "passive"))
    )
    (net (code "12") (name "GND") (class "Default")
      (node (ref "C10") (pin "2") (pinfunction "2_2") (pintype "power_in"))
      (node (ref "C11") (pin "2") (pinfunction "2_2") (pintype "power_in"))
      (node (ref "C12") (pin "2") (pinfunction "2_2") (pintype "power_in"))
      (node (ref "C13") (pin "1") (pinfunction "1_1") (pintype "power_in"))
      (node (ref "C15") (pin "1") (pinfunction "1_1") (pintype "power_in"))
      (node (ref "C17") (pin "1") (pinfunction "1_1") (pintype "power_in"))
      (node (ref "C2") (pin "1") (pinfunction "1_1") (pintype "power_in"))
      (node (ref "C20") (pin "1") (pinfunction "1_1") (pintype "power_in"))
      (node (ref "C21") (pin "1") (pinfunction "1_1") (pintype "power_in"))
      (node (ref "C22") (pin "1") (pinfunction "1_1") (pintype "power_in"))
      (node (ref "C23") (pin "1") (pinfunction "1_1") (pintype "power_in"))
      (node (ref "C24") (pin "1") (pinfunction "1_1") (pintype "power_in"))
      (node (ref "C25") (pin "1") (pinfunction "1_1") (pintype "power_in"))
      (node (ref "C26") (pin "1") (pinfunction "1_1") (pintype "power_in"))
      (node (ref "C27") (pin "1") (pinfunction "1_1") (pintype "power_in"))
      (node (ref "C28") (pin "1") (pinfunction "1_1") (pintype "power_in"))
      (node (ref "C29") (pin "1") (pinfunction "1_1") (pintype "power_in"))
      (node (ref "C3") (pin "2") (pinfunction "2_2") (pintype "power_in"))
      (node (ref "C4") (pin "2") (pinfunction "2_2") (pintype "power_in"))
      (node (ref "C5") (pin "2") (pinfunction "2_2") (pintype "power_in"))
      (node (ref "C6") (pin "2") (pinfunction "2_2") (pintype "power_in"))
      (node (ref "C7") (pin "1") (pinfunction "1_1") (pintype "power_in"))
      (node (ref "C8") (pin "1") (pinfunction "1_1") (pintype "power_in"))
      (node (ref "C9") (pin "2") (pinfunction "2_2") (pintype "power_in"))
      (node (ref "D1") (pin "3") (pinfunction "GND_3") (pintype "passive"))
      (node (ref "D2") (pin "2") (pinfunction "V-_2") (pintype "power_in"))
      (node (ref "D3") (pin "2") (pinfunction "V-_2") (pintype "power_in"))
      (node (ref "D4") (pin "2") (pinfunction "GND_2") (pintype "passive"))
      (node (ref "D5") (pin "0") (pinfunction "GND_0") (pintype "passive"))
      (node (ref "D5") (pin "1") (pinfunction "RTN_1") (pintype "passive"))
      (node (ref "R12") (pin "1") (pinfunction "1_1") (pintype "passive"))
      (node (ref "R15") (pin "2") (pinfunction "2_2") (pintype "passive"))
      (node (ref "R16") (pin "1") (pinfunction "1_1") (pintype "passive"))
      (node (ref "R19") (pin "2") (pinfunction "2_2") (pintype "passive"))
      (node (ref "R21") (pin "1") (pinfunction "1_1") (pintype "passive"))
      (node (ref "R25") (pin "1") (pinfunction "1_1") (pintype "passive"))
      (node (ref "R27") (pin "1") (pinfunction "1_1") (pintype "passive"))
      (node (ref "R28") (pin "2") (pinfunction "2_2") (pintype "passive"))
      (node (ref "R36") (pin "1") (pinfunction "1_1") (pintype "passive"))
      (node (ref "R38") (pin "1") (pinfunction "1_1") (pintype "passive"))
      (node (ref "R39") (pin "1") (pinfunction "1_1") (pintype "passive"))
      (node (ref "R5") (pin "1") (pinfunction "1_1") (pintype "passive"))
      (node (ref "R6") (pin "1") (pinfunction "1_1") (pintype "passive"))
      (node (ref "R8") (pin "1") (pinfunction "1_1") (pintype "passive"))
      (node (ref "R9") (pin "1") (pinfunction "1_1") (pintype "passive"))
      (node (ref "VD3") (pin "1") (pinfunction "1_1") (pintype "passive"))
      (node (ref "VT2") (pin "3") (pinfunction "S_3") (pintype "passive"))
      (node (ref "VT3") (pin "2") (pinfunction "S_2") (pintype "passive"))
    )
    (net (code "13") (name "Net-(C14-Pad1)") (class "Default")
      (node (ref "C14") (pin "1") (pinfunction "1_1") (pintype "power_in"))
      (node (ref "R24") (pin "1") (pinfunction "1_1") (pintype "passive"))
      (node (ref "R25") (pin "2") (pinfunction "2_2") (pintype "passive"))
    )
    (net (code "14") (name "Net-(C14-Pad2)") (class "Default")
      (node (ref "C14") (pin "2") (pinfunction "2_2") (pintype "power_in"))
      (node (ref "R17") (pin "1") (pinfunction "1_1") (pintype "passive"))
      (node (ref "R18") (pin "2") (pinfunction "2_2") (pintype "passive"))
    )
    (net (code "15") (name "Net-(C16-Pad1)") (class "Default")
      (node (ref "C16") (pin "1") (pinfunction "1_1") (pintype "power_in"))
      (node (ref "R28") (pin "1") (pinfunction "1_1") (pintype "passive"))
      (node (ref "R29") (pin "2") (pinfunction "2_2") (pintype "passive"))
    )
    (net (code "16") (name "Net-(C16-Pad2)") (class "Default")
      (node (ref "C16") (pin "2") (pinfunction "2_2") (pintype "power_in"))
      (node (ref "R22") (pin "1") (pinfunction "1_1") (pintype "passive"))
      (node (ref "R23") (pin "2") (pinfunction "2_2") (pintype "passive"))
    )
    (net (code "17") (name "Net-(D1-HO)") (class "Default")
      (node (ref "D1") (pin "7") (pinfunction "HO_7") (pintype "passive"))
      (node (ref "R2") (pin "2") (pinfunction "2_2") (pintype "passive"))
    )
    (net (code "18") (name "Net-(D1-LO)") (class "Default")
      (node (ref "D1") (pin "4") (pinfunction "LO_4") (pintype "passive"))
      (node (ref "R4") (pin "2") (pinfunction "2_2") (pintype "passive"))
    )
    (net (code "19") (name "Net-(D1-VB)") (class "Default")
      (node (ref "C1") (pin "2") (pinfunction "2_2") (pintype "power_in"))
      (node (ref "D1") (pin "8") (pinfunction "VB_8") (pintype "passive"))
      (node (ref "VD1") (pin "2") (pinfunction "2_2") (pintype "passive"))
    )
    (net (code "20") (name "Net-(D1-VS)") (class "Default")
      (node (ref "C1") (pin "1") (pinfunction "1_1") (pintype "power_in"))
      (node (ref "D1") (pin "6") (pinfunction "VS_6") (pintype "passive"))
      (node (ref "L1") (pin "2") (pinfunction "2_2") (pintype "passive"))
      (node (ref "R3") (pin "1") (pinfunction "1_1") (pintype "passive"))
      (node (ref "VT1") (pin "3") (pinfunction "S_3") (pintype "passive"))
      (node (ref "VT2") (pin "2") (pinfunction "D_2") (pintype "passive"))
    )
    (net (code "21") (name "Net-(D2-IN+)") (class "Default")
      (node (ref "D2") (pin "3") (pinfunction "IN+_3") (pintype "input"))
      (node (ref "R15") (pin "1") (pinfunction "1_1") (pintype "passive"))
      (node (ref "R17") (pin "2") (pinfunction "2_2") (pintype "passive"))
    )
    (net (code "22") (name "Net-(D2-IN-)") (class "Default")
      (node (ref "D2") (pin "4") (pinfunction "IN-_4") (pintype "input"))
      (node (ref "R24") (pin "2") (pinfunction "2_2") (pintype "passive"))
      (node (ref "R30") (pin "1") (pinfunction "1_1") (pintype "passive"))
    )
    (net (code "23") (name "Net-(D2-OUT)") (class "Default")
      (node (ref "D2") (pin "1") (pinfunction "OUT_1") (pintype "power_in"))
      (node (ref "R20") (pin "1") (pinfunction "1_1") (pintype "passive"))
      (node (ref "R30") (pin "2") (pinfunction "2_2") (pintype "passive"))
    )
    (net (code "24") (name "Net-(D3-IN+)") (class "Default")
      (node (ref "D3") (pin "3") (pinfunction "IN+_3") (pintype "input"))
      (node (ref "R19") (pin "1") (pinfunction "1_1") (pintype "passive"))
      (node (ref "R23") (pin "1") (pinfunction "1_1") (pintype "passive"))
    )
    (net (code "25") (name "Net-(D3-IN-)") (class "Default")
      (node (ref "D3") (pin "4") (pinfunction "IN-_4") (pintype "input"))
      (node (ref "R29") (pin "1") (pinfunction "1_1") (pintype "passive"))
      (node (ref "R31") (pin "2") (pinfunction "2_2") (pintype "passive"))
    )
    (net (code "26") (name "Net-(D3-OUT)") (class "Default")
      (node (ref "D3") (pin "1") (pinfunction "OUT_1") (pintype "power_in"))
      (node (ref "R26") (pin "2") (pinfunction "2_2") (pintype "passive"))
      (node (ref "R31") (pin "1") (pinfunction "1_1") (pintype "passive"))
    )
    (net (code "27") (name "Net-(D4-BS)") (class "Default")
      (node (ref "C18") (pin "2") (pinfunction "2_2") (pintype "power_in"))
      (node (ref "D4") (pin "1") (pinfunction "BS_1") (pintype "passive"))
    )
    (net (code "28") (name "Net-(D4-EN)") (class "Default")
      (node (ref "D4") (pin "4") (pinfunction "EN_4") (pintype "input"))
      (node (ref "R32") (pin "1") (pinfunction "1_1") (pintype "passive"))
    )
    (net (code "29") (name "Net-(D4-FB)") (class "Default")
      (node (ref "D4") (pin "3") (pinfunction "FB_3") (pintype "input"))
      (node (ref "R33") (pin "2") (pinfunction "2_2") (pintype "passive"))
      (node (ref "R36") (pin "2") (pinfunction "2_2") (pintype "passive"))
    )
    (net (code "30") (name "Net-(D4-SW)") (class "Default")
      (node (ref "C18") (pin "1") (pinfunction "1_1") (pintype "power_in"))
      (node (ref "D4") (pin "6") (pinfunction "SW_6") (pintype "passive"))
      (node (ref "L2") (pin "2") (pinfunction "2_2") (pintype "passive"))
      (node (ref "VD3") (pin "2") (pinfunction "2_2") (pintype "passive"))
    )
    (net (code "31") (name "Net-(D5-BST)") (class "Default")
      (node (ref "C19") (pin "2") (pinfunction "2_2") (pintype "power_in"))
      (node (ref "D5") (pin "7") (pinfunction "BST_7") (pintype "passive"))
    )
    (net (code "32") (name "Net-(D5-FB)") (class "Default")
      (node (ref "D5") (pin "5") (pinfunction "FB_5") (pintype "input"))
      (node (ref "R37") (pin "2") (pinfunction "2_2") (pintype "passive"))
      (node (ref "R39") (pin "2") (pinfunction "2_2") (pintype "passive"))
    )
    (net (code "33") (name "Net-(D5-RON)") (class "Default")
      (node (ref "D5") (pin "4") (pinfunction "RON_4") (pintype "input"))
      (node (ref "R34") (pin "1") (pinfunction "1_1") (pintype "passive"))
    )
    (net (code "34") (name "Net-(D5-SW)") (class "Default")
      (node (ref "C19") (pin "1") (pinfunction "1_1") (pintype "power_in"))
      (node (ref "D5") (pin "8") (pinfunction "SW_8") (pintype "passive"))
      (node (ref "L3") (pin "2") (pinfunction "2_2") (pintype "passive"))
    )
    (net (code "35") (name "Net-(D5-UVLO)") (class "Default")
      (node (ref "D5") (pin "3") (pinfunction "UVLO_3") (pintype "passive"))
      (node (ref "R35") (pin "1") (pinfunction "1_1") (pintype "passive"))
      (node (ref "R38") (pin "2") (pinfunction "2_2") (pintype "passive"))
    )
    (net (code "36") (name "Net-(D5-VCC)") (class "Default")
      (node (ref "C27") (pin "2") (pinfunction "2_2") (pintype "power_in"))
      (node (ref "D5") (pin "6") (pinfunction "VCC_6") (pintype "passive"))
      (node (ref "VD4") (pin "2") (pinfunction "2_2") (pintype "passive"))
    )
    (net (code "37") (name "Net-(R1-Pad1)") (class "Default")
      (node (ref "R1") (pin "1") (pinfunction "1_1") (pintype "passive"))
      (node (ref "VD1") (pin "1") (pinfunction "1_1") (pintype "passive"))
    )
    (net (code "38") (name "Net-(R18-Pad1)") (class "Default")
      (node (ref "R18") (pin "1") (pinfunction "1_1") (pintype "passive"))
      (node (ref "R21") (pin "2") (pinfunction "2_2") (pintype "passive"))
      (node (ref "X1") (pin "2") (pinfunction "2_2") (pintype "passive"))
    )
    (net (code "39") (name "Net-(VD2-A)") (class "Default")
      (node (ref "R22") (pin "2") (pinfunction "2_2") (pintype "passive"))
      (node (ref "R27") (pin "2") (pinfunction "2_2") (pintype "passive"))
      (node (ref "VD2") (pin "1") (pinfunction "A_1") (pintype "passive"))
      (node (ref "VT4") (pin "3") (pinfunction "S_3") (pintype "passive"))
    )
    (net (code "40") (name "Net-(VD2-C)") (class "Default")
      (node (ref "R14") (pin "1") (pinfunction "1_1") (pintype "passive"))
      (node (ref "VD2") (pin "2") (pinfunction "C_2") (pintype "passive"))
      (node (ref "VT4") (pin "1") (pinfunction "G_1") (pintype "passive"))
    )
    (net (code "41") (name "Net-(VT1-G)") (class "Default")
      (node (ref "R2") (pin "1") (pinfunction "1_1") (pintype "passive"))
      (node (ref "R3") (pin "2") (pinfunction "2_2") (pintype "passive"))
      (node (ref "VT1") (pin "1") (pinfunction "G_1") (pintype "passive"))
    )
    (net (code "42") (name "Net-(VT2-G)") (class "Default")
      (node (ref "R4") (pin "1") (pinfunction "1_1") (pintype "passive"))
      (node (ref "R8") (pin "2") (pinfunction "2_2") (pintype "passive"))
      (node (ref "VT2") (pin "1") (pinfunction "G_1") (pintype "passive"))
    )
    (net (code "43") (name "Net-(VT3-D)") (class "Default")
      (node (ref "R10") (pin "1") (pinfunction "1_1") (pintype "passive"))
      (node (ref "VT3") (pin "3") (pinfunction "D_3") (pintype "passive"))
    )
    (net (code "44") (name "Net-(VT3-G)") (class "Default")
      (node (ref "R11") (pin "2") (pinfunction "2_2") (pintype "passive"))
      (node (ref "R12") (pin "2") (pinfunction "2_2") (pintype "passive"))
      (node (ref "VT3") (pin "1") (pinfunction "G_1") (pintype "passive"))
    )
    (net (code "45") (name "Net-(VT4-D)") (class "Default")
      (node (ref "VT4") (pin "2") (pinfunction "D_2") (pintype "passive"))
      (node (ref "X2") (pin "2") (pinfunction "2_2") (pintype "passive"))
    )
  )
)
